# 03_Periphs.net
KiCad netlist of a schematic drawn in Altium Designer
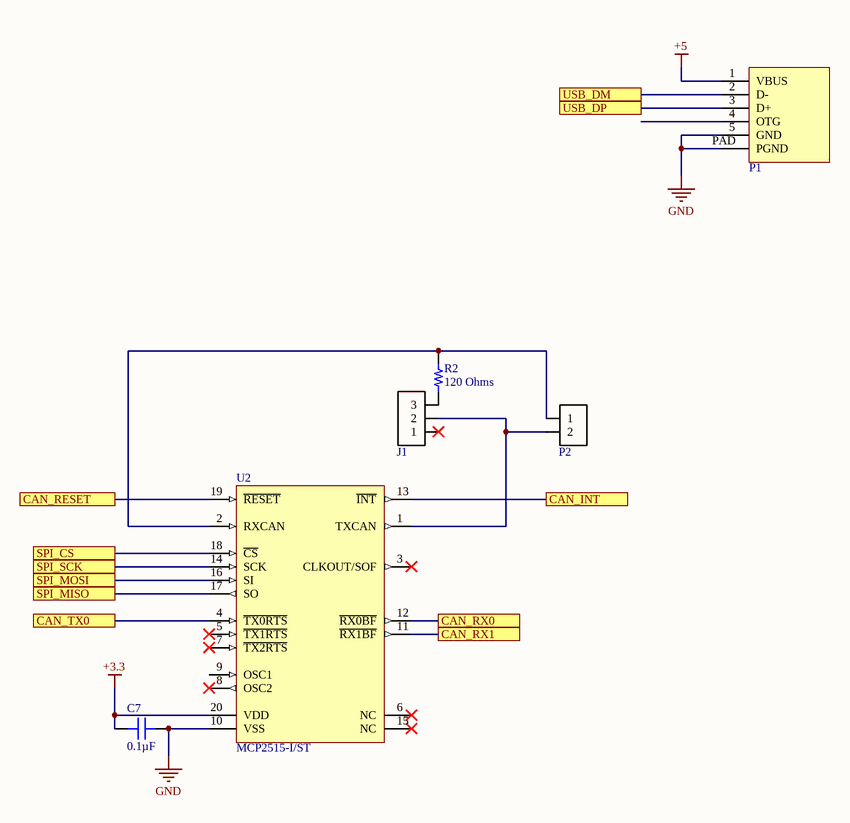
[diagram p0: 03_Periphs.SchDoc]

(export (version "E")
  (design (tool "Eeschema 10.0.6"))
  (components
    (comp (ref "C7")
      (value "0.1µF")
      (footprint "CAP 0805_2012")
      (description "CAP CER 0805 0.1UF 50V X7R")
      (fields (field (name "PART NUMBER") "C0805X104K5RAC3316") (field (name "MANUFACTURER") "KEMET"))
      (libsource (lib "Celestial Altium Library - altium_library") (part "Capacitor"))
    )
    (comp (ref "J1")
      (value "conn-3x1_0")
      (footprint "HDDR_3x1_0")
      (description "Header, 3x1, 0.1\"")
      (fields (field (name "PART NUMBER") "CONN-00037"))
      (libsource (lib "cwrubotix_library") (part "conn-3x1_0"))
    )
    (comp (ref "P1")
      (value "usb_micro_b")
      (footprint "10118192")
      (description "USB Micro B Type Receptacle")
      (fields (field (name "PART NUMBER") "CONN-00011") (field (name "MANUFACTURER") "Amphenol"))
      (libsource (lib "cwrubotix_library") (part "usb_micro_b"))
    )
    (comp (ref "P2")
      (value "conn-2x1_0")
      (footprint "TERM_3.50MM_2x1_0")
      (description "Term Blk, 2 Pos, 8A, 3.5mm Pitch, Screwless")
      (fields (field (name "PART NUMBER") "CONN-00023") (field (name "MANUFACTURER") "Phoenix Contact"))
      (libsource (lib "cwrubotix_library") (part "conn-2x1_0"))
    )
    (comp (ref "R2")
      (value "120 Ohms")
      (footprint "RES 0805_2012")
      (description "CRGCQ 0805 120R 1%")
      (fields
        (field (name "PART NUMBER") "CRGCQ0805F120R")
        (field (name "MANUFACTURER") "TE Connectivity Passive Product")
      )
      (libsource (lib "Celestial Altium Library - altium_library") (part "Resistor"))
    )
    (comp (ref "U2")
      (value "MCP2515-I/ST")
      (footprint "TSSOP-ST20_N")
      (description "Stand-Alone CAN Controller With SPI Interface, 20-Pin TSSOP, Industrial Temperature")
      (libsource (lib "Altium Content Vault") (part "COM-CAN-MCP2515-20"))
    )
  )
  (nets
    (net (code "1") (name "+3.3") (class "Default")
      (node (ref "C7") (pin "2") (pinfunction "2_2") (pintype "passive"))
      (node (ref "U2") (pin "20") (pinfunction "VDD_20") (pintype "power_in"))
    )
    (net (code "2") (name "+5") (class "Default")
      (node (ref "P1") (pin "1") (pinfunction "VBUS_1") (pintype "passive"))
    )
    (net (code "3") (name "/CAN_INT") (class "Default")
      (node (ref "U2") (pin "13") (pinfunction "~{INT}_13") (pintype "output"))
    )
    (net (code "4") (name "/CAN_RESET") (class "Default")
      (node (ref "U2") (pin "19") (pinfunction "~{RESET}_19") (pintype "input"))
    )
    (net (code "5") (name "/CAN_RX0") (class "Default")
      (node (ref "U2") (pin "12") (pinfunction "~{RX0BF}_12") (pintype "output"))
    )
    (net (code "6") (name "/CAN_RX1") (class "Default")
      (node (ref "U2") (pin "11") (pinfunction "~{RX1BF}_11") (pintype "output"))
    )
    (net (code "7") (name "/CAN_TX0") (class "Default")
      (node (ref "U2") (pin "4") (pinfunction "~{TX0RTS}_4") (pintype "input"))
    )
    (net (code "8") (name "/SPI_CS") (class "Default")
      (node (ref "U2") (pin "18") (pinfunction "~{CS}_18") (pintype "input"))
    )
    (net (code "9") (name "/SPI_MISO") (class "Default")
      (node (ref "U2") (pin "17") (pinfunction "SO_17") (pintype "output"))
    )
    (net (code "10") (name "/SPI_MOSI") (class "Default")
      (node (ref "U2") (pin "16") (pinfunction "SI_16") (pintype "input"))
    )
    (net (code "11") (name "/SPI_SCK") (class "Default")
      (node (ref "U2") (pin "14") (pinfunction "SCK_14") (pintype "input"))
    )
    (net (code "12") (name "/USB_DM") (class "Default")
      (node (ref "P1") (pin "2") (pinfunction "D-_2") (pintype "passive"))
    )
    (net (code "13") (name "/USB_DP") (class "Default")
      (node (ref "P1") (pin "3") (pinfunction "D+_3") (pintype "passive"))
    )
    (net (code "14") (name "GND") (class "Default")
      (node (ref "C7") (pin "1") (pinfunction "1_1") (pintype "passive"))
      (node (ref "P1") (pin "5") (pinfunction "GND_5") (pintype "passive"))
      (node (ref "P1") (pin "PAD") (pinfunction "PGND_PAD") (pintype "passive"))
      (node (ref "U2") (pin "10") (pinfunction "VSS_10") (pintype "power_in"))
    )
    (net (code "15") (name "Net-(J1-Pad3)") (class "Default")
      (node (ref "J1") (pin "3") (pinfunction "3_3") (pintype "passive"))
      (node (ref "R2") (pin "1") (pinfunction "1_1") (pintype "passive"))
    )
    (net (code "16") (name "Net-(U2-RXCAN)") (class "Default")
      (node (ref "P2") (pin "1") (pinfunction "1_1") (pintype "passive"))
      (node (ref "R2") (pin "2") (pinfunction "2_2") (pintype "passive"))
      (node (ref "U2") (pin "2") (pinfunction "RXCAN_2") (pintype "input"))
    )
    (net (code "17") (name "Net-(U2-TXCAN)") (class "Default")
      (node (ref "J1") (pin "2") (pinfunction "2_2") (pintype "passive"))
      (node (ref "P2") (pin "2") (pinfunction "2_2") (pintype "passive"))
      (node (ref "U2") (pin "1") (pinfunction "TXCAN_1") (pintype "output"))
    )
    (net (code "18") (name "unconnected-(J1-Pad1)") (class "Default")
      (node (ref "J1") (pin "1") (pinfunction "1_1") (pintype "passive+no_connect"))
    )
    (net (code "19") (name "unconnected-(P1-OTG-Pad4)") (class "Default")
      (node (ref "P1") (pin "4") (pinfunction "OTG_4") (pintype "passive"))
    )
    (net (code "20") (name "unconnected-(U2-CLKOUT{slash}SOF-Pad3)") (class "Default")
      (node (ref "U2") (pin "3") (pinfunction "CLKOUT/SOF_3") (pintype "output+no_connect"))
    )
    (net (code "21") (name "unconnected-(U2-NC-Pad6)") (class "Default")
      (node (ref "U2") (pin "6") (pinfunction "NC_6") (pintype "passive+no_connect"))
    )
    (net (code "22") (name "unconnected-(U2-NC-Pad15)") (class "Default")
      (node (ref "U2") (pin "15") (pinfunction "NC_15") (pintype "passive+no_connect"))
    )
    (net (code "23") (name "unconnected-(U2-OSC1-Pad9)") (class "Default")
      (node (ref "U2") (pin "9") (pinfunction "OSC1_9") (pintype "input"))
    )
    (net (code "24") (name "unconnected-(U2-OSC2-Pad8)") (class "Default")
      (node (ref "U2") (pin "8") (pinfunction "OSC2_8") (pintype "output+no_connect"))
    )
    (net (code "25") (name "unconnected-(U2-~{TX1RTS}-Pad5)") (class "Default")
      (node (ref "U2") (pin "5") (pinfunction "~{TX1RTS}_5") (pintype "input+no_connect"))
    )
    (net (code "26") (name "unconnected-(U2-~{TX2RTS}-Pad7)") (class "Default")
      (node (ref "U2") (pin "7") (pinfunction "~{TX2RTS}_7") (pintype "input+no_connect"))
    )
  )
)
